# battery_monitor_6803-2.net
KiCad netlist of a schematic drawn in EAGLE
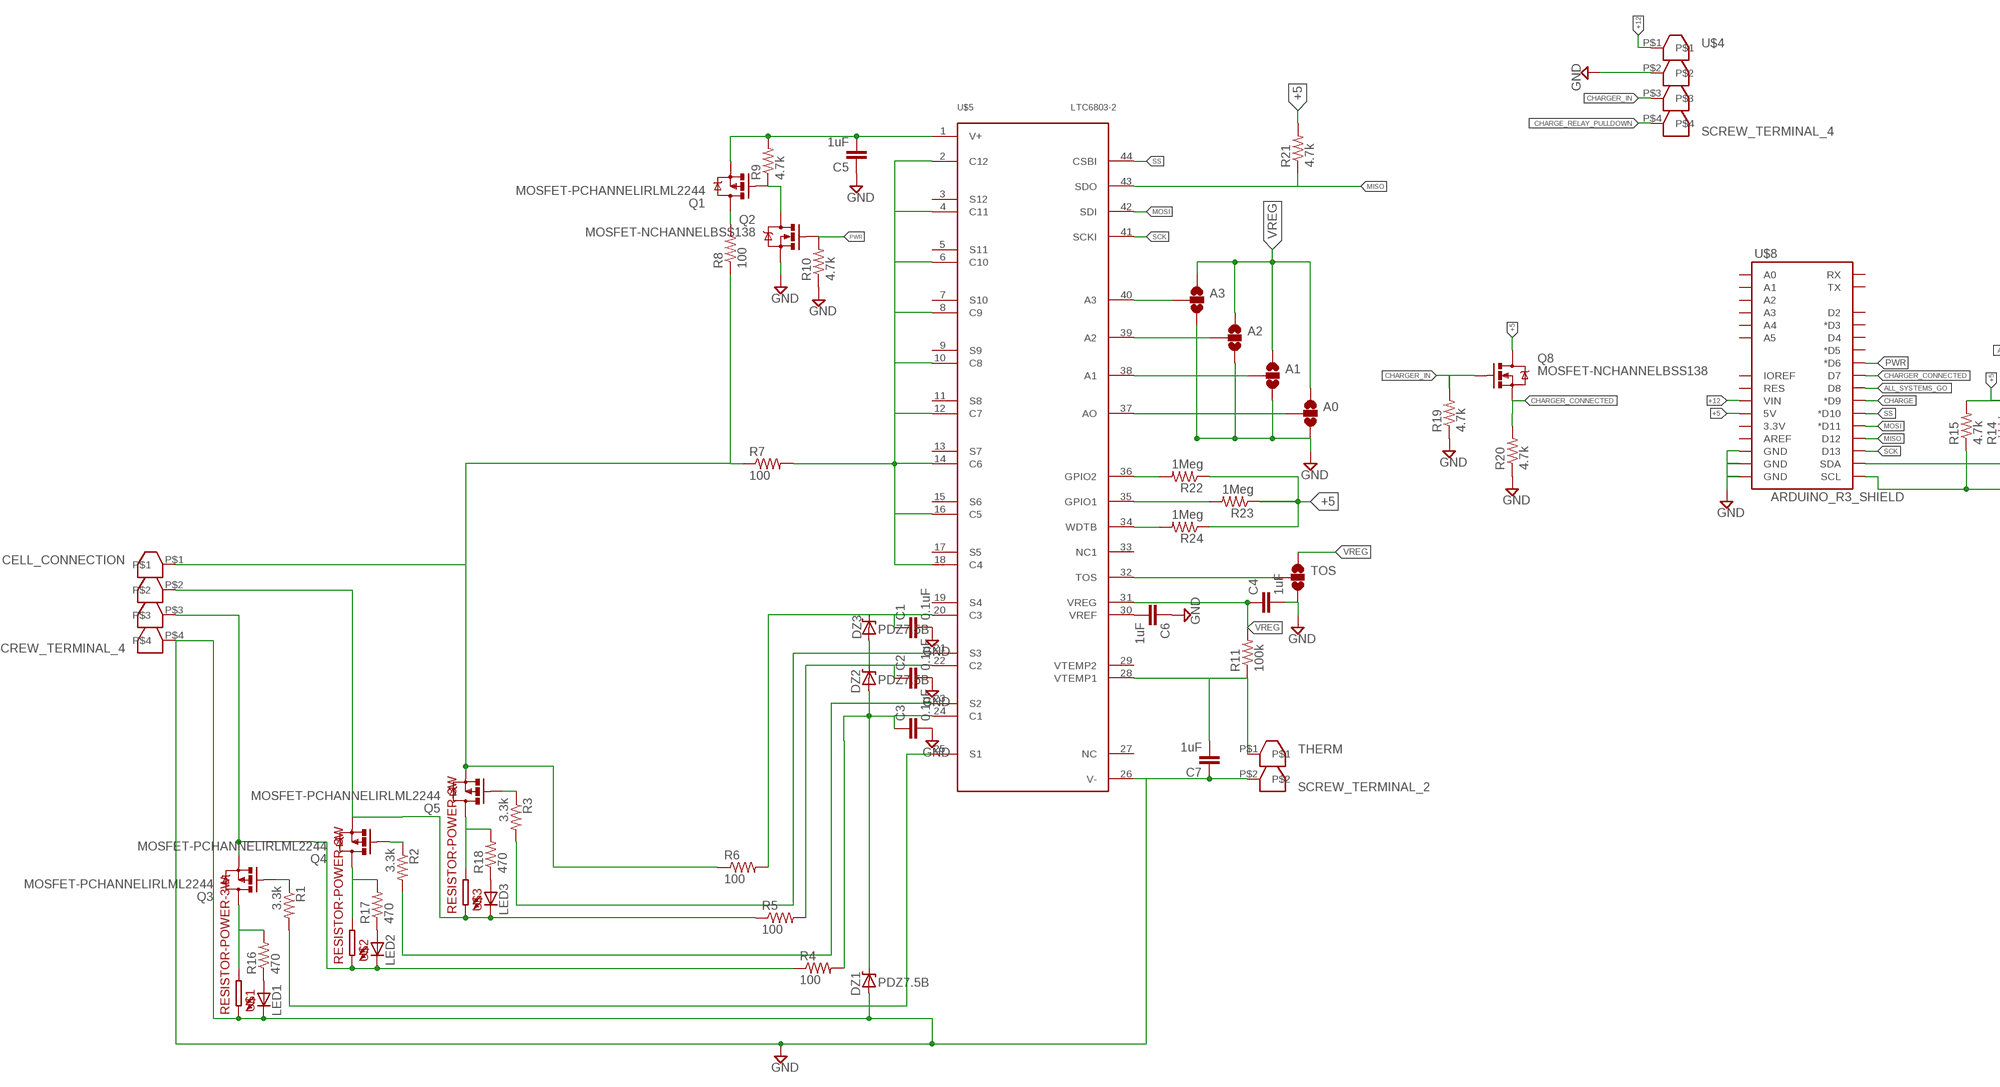
[diagram p0: schematic, sheet 1, part 1 of 2]
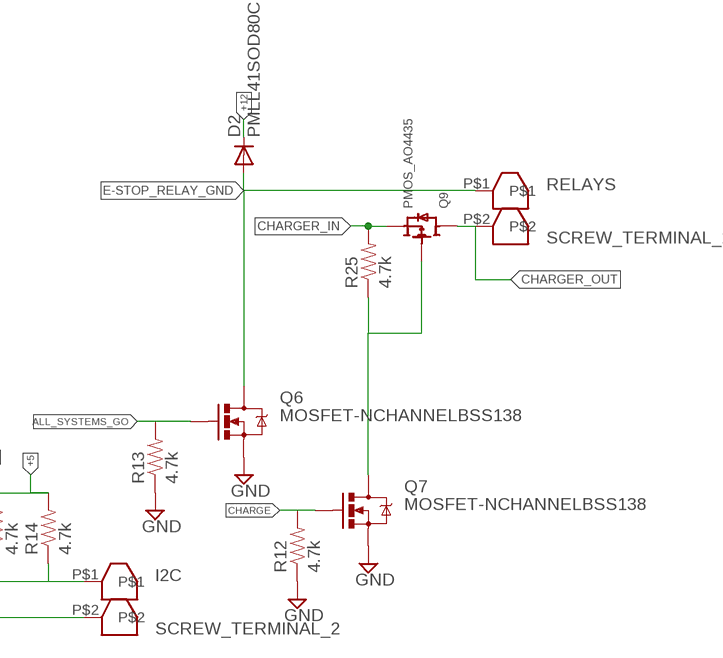
[diagram p1: schematic, sheet 1, part 2 of 2]

(export (version "E")
  (design (tool "Eeschema 10.0.6"))
  (components
    (comp (ref "A0")
      (value "SOLDERJUMPER_2WAYS")
      (footprint "eagle-import:SJ_3")
      (libsource (lib "eagle-import") (part "SOLDERJUMPER_2WAYS"))
    )
    (comp (ref "A1")
      (value "SOLDERJUMPER_2WAYS")
      (footprint "eagle-import:SJ_3")
      (libsource (lib "eagle-import") (part "SOLDERJUMPER_2WAYS"))
    )
    (comp (ref "A2")
      (value "SOLDERJUMPER_2WAYS")
      (footprint "eagle-import:SJ_3")
      (libsource (lib "eagle-import") (part "SOLDERJUMPER_2WAYS"))
    )
    (comp (ref "A3")
      (value "SOLDERJUMPER_2WAYS")
      (footprint "eagle-import:SJ_3")
      (libsource (lib "eagle-import") (part "SOLDERJUMPER_2WAYS"))
    )
    (comp (ref "C1")
      (value "0.1uF")
      (footprint "eagle-import:0603-CAP")
      (libsource (lib "eagle-import") (part "0.1UF-100V-10%(0603)"))
    )
    (comp (ref "C2")
      (value "0.1uF")
      (footprint "eagle-import:0603-CAP")
      (libsource (lib "eagle-import") (part "0.1UF-100V-10%(0603)"))
    )
    (comp (ref "C3")
      (value "0.1uF")
      (footprint "eagle-import:0603-CAP")
      (libsource (lib "eagle-import") (part "0.1UF-100V-10%(0603)"))
    )
    (comp (ref "C4")
      (value "1uF")
      (footprint "eagle-import:0603-CAP")
      (fields (field (name "PROD_ID") "CAP-08390"))
      (libsource (lib "eagle-import") (part "0.1UF-100V-10%(0603)"))
    )
    (comp (ref "C5")
      (value "1uF")
      (footprint "eagle-import:0603-CAP")
      (fields (field (name "PROD_ID") "CAP-08390"))
      (libsource (lib "eagle-import") (part "0.1UF-100V-10%(0603)"))
    )
    (comp (ref "C6")
      (value "1uF")
      (footprint "eagle-import:0603-CAP")
      (fields (field (name "PROD_ID") "CAP-08390"))
      (libsource (lib "eagle-import") (part "0.1UF-100V-10%(0603)"))
    )
    (comp (ref "C7")
      (value "1uF")
      (footprint "eagle-import:0603-CAP")
      (fields (field (name "PROD_ID") "CAP-08390"))
      (libsource (lib "eagle-import") (part "0.1UF-100V-10%(0603)"))
    )
    (comp (ref "CELL_CONNECTION")
      (value "SCREW_TERMINAL_4")
      (footprint "eagle-import:SCREW_TERMINAL_4")
      (libsource (lib "eagle-import") (part "SCREW_TERMINAL_4"))
    )
    (comp (ref "D2")
      (value "PMLL41SOD80C")
      (footprint "eagle-import:SOD80C")
      (libsource (lib "eagle-import") (part "PMLL41SOD80C"))
    )
    (comp (ref "DZ1")
      (value "PDZ7.5B")
      (footprint "eagle-import:SOD-323")
      (libsource (lib "eagle-import") (part "DIODE-ZENER-BZT52"))
    )
    (comp (ref "DZ2")
      (value "PDZ7.5B")
      (footprint "eagle-import:SOD-323")
      (libsource (lib "eagle-import") (part "DIODE-ZENER-BZT52"))
    )
    (comp (ref "DZ3")
      (value "PDZ7.5B")
      (footprint "eagle-import:SOD-323")
      (libsource (lib "eagle-import") (part "DIODE-ZENER-BZT52"))
    )
    (comp (ref "I2C")
      (value "SCREW_TERMINAL_2")
      (footprint "eagle-import:SCREW_TERMINAL_2")
      (libsource (lib "eagle-import") (part "SCREW_TERMINAL_2"))
    )
    (comp (ref "LED1")
      (value "LED0603")
      (footprint "eagle-import:LED-0603")
      (libsource (lib "eagle-import") (part "LED0603"))
    )
    (comp (ref "LED2")
      (value "LED0603")
      (footprint "eagle-import:LED-0603")
      (libsource (lib "eagle-import") (part "LED0603"))
    )
    (comp (ref "LED3")
      (value "LED0603")
      (footprint "eagle-import:LED-0603")
      (libsource (lib "eagle-import") (part "LED0603"))
    )
    (comp (ref "Q1")
      (value "MOSFET-PCHANNELIRLML2244")
      (footprint "eagle-import:SOT23-3")
      (libsource (lib "eagle-import") (part "MOSFET-PCHANNELIRLML2244"))
    )
    (comp (ref "Q2")
      (value "MOSFET-NCHANNELBSS138")
      (footprint "eagle-import:SOT23")
      (libsource (lib "eagle-import") (part "MOSFET-NCHANNELBSS138"))
    )
    (comp (ref "Q3")
      (value "MOSFET-PCHANNELIRLML2244")
      (footprint "eagle-import:SOT23-3")
      (libsource (lib "eagle-import") (part "MOSFET-PCHANNELIRLML2244"))
    )
    (comp (ref "Q4")
      (value "MOSFET-PCHANNELIRLML2244")
      (footprint "eagle-import:SOT23-3")
      (libsource (lib "eagle-import") (part "MOSFET-PCHANNELIRLML2244"))
    )
    (comp (ref "Q5")
      (value "MOSFET-PCHANNELIRLML2244")
      (footprint "eagle-import:SOT23-3")
      (libsource (lib "eagle-import") (part "MOSFET-PCHANNELIRLML2244"))
    )
    (comp (ref "Q6")
      (value "MOSFET-NCHANNELBSS138")
      (footprint "eagle-import:SOT23")
      (libsource (lib "eagle-import") (part "MOSFET-NCHANNELBSS138"))
    )
    (comp (ref "Q7")
      (value "MOSFET-NCHANNELBSS138")
      (footprint "eagle-import:SOT23")
      (libsource (lib "eagle-import") (part "MOSFET-NCHANNELBSS138"))
    )
    (comp (ref "Q8")
      (value "MOSFET-NCHANNELBSS138")
      (footprint "eagle-import:SOT23")
      (fields (field (name "PROD_ID") "TRANS-00830"))
      (libsource (lib "eagle-import") (part "MOSFET-NCHANNELBSS138"))
    )
    (comp (ref "Q9")
      (value "PMOS_AO4435")
      (footprint "eagle-import:SOIC8")
      (libsource (lib "eagle-import") (part "PMOS_AO4435"))
    )
    (comp (ref "R1")
      (value "3.3k")
      (footprint "eagle-import:0603-RES")
      (libsource (lib "eagle-import") (part "3.3KOHM1/10W1%(0603)"))
    )
    (comp (ref "R2")
      (value "3.3k")
      (footprint "eagle-import:0603-RES")
      (libsource (lib "eagle-import") (part "3.3KOHM1/10W1%(0603)"))
    )
    (comp (ref "R3")
      (value "3.3k")
      (footprint "eagle-import:0603-RES")
      (libsource (lib "eagle-import") (part "3.3KOHM1/10W1%(0603)"))
    )
    (comp (ref "R4")
      (value "100")
      (footprint "eagle-import:0603-RES")
      (libsource (lib "eagle-import") (part "3.3KOHM1/10W1%(0603)"))
    )
    (comp (ref "R5")
      (value "100")
      (footprint "eagle-import:0603-RES")
      (libsource (lib "eagle-import") (part "3.3KOHM1/10W1%(0603)"))
    )
    (comp (ref "R6")
      (value "100")
      (footprint "eagle-import:0603-RES")
      (libsource (lib "eagle-import") (part "3.3KOHM1/10W1%(0603)"))
    )
    (comp (ref "R7")
      (value "100")
      (footprint "eagle-import:0603-RES")
      (libsource (lib "eagle-import") (part "3.3KOHM1/10W1%(0603)"))
    )
    (comp (ref "R8")
      (value "100")
      (footprint "eagle-import:0603-RES")
      (libsource (lib "eagle-import") (part "3.3KOHM1/10W1%(0603)"))
    )
    (comp (ref "R9")
      (value "4.7k")
      (footprint "eagle-import:0603-RES")
      (libsource (lib "eagle-import") (part "3.3KOHM1/10W1%(0603)"))
    )
    (comp (ref "R10")
      (value "4.7k")
      (footprint "eagle-import:0603-RES")
      (libsource (lib "eagle-import") (part "3.3KOHM1/10W1%(0603)"))
    )
    (comp (ref "R11")
      (value "100k")
      (footprint "eagle-import:0603-RES")
      (libsource (lib "eagle-import") (part "3.3KOHM1/10W1%(0603)"))
    )
    (comp (ref "R12")
      (value "4.7k")
      (footprint "eagle-import:0603-RES")
      (libsource (lib "eagle-import") (part "3.3KOHM1/10W1%(0603)"))
    )
    (comp (ref "R13")
      (value "4.7k")
      (footprint "eagle-import:0603-RES")
      (libsource (lib "eagle-import") (part "3.3KOHM1/10W1%(0603)"))
    )
    (comp (ref "R14")
      (value "4.7k")
      (footprint "eagle-import:0603-RES")
      (libsource (lib "eagle-import") (part "3.3KOHM1/10W1%(0603)"))
    )
    (comp (ref "R15")
      (value "4.7k")
      (footprint "eagle-import:0603-RES")
      (libsource (lib "eagle-import") (part "3.3KOHM1/10W1%(0603)"))
    )
    (comp (ref "R16")
      (value "470")
      (footprint "eagle-import:0603-RES")
      (fields (field (name "PROD_ID") "RES-07851"))
      (libsource (lib "eagle-import") (part "3.3KOHM1/10W1%(0603)"))
    )
    (comp (ref "R17")
      (value "470")
      (footprint "eagle-import:0603-RES")
      (fields (field (name "PROD_ID") "RES-07851"))
      (libsource (lib "eagle-import") (part "3.3KOHM1/10W1%(0603)"))
    )
    (comp (ref "R18")
      (value "470")
      (footprint "eagle-import:0603-RES")
      (fields (field (name "PROD_ID") "RES-07851"))
      (libsource (lib "eagle-import") (part "3.3KOHM1/10W1%(0603)"))
    )
    (comp (ref "R19")
      (value "4.7k")
      (footprint "eagle-import:0603-RES")
      (fields (field (name "PROD_ID") "RES-07851"))
      (libsource (lib "eagle-import") (part "3.3KOHM1/10W1%(0603)"))
    )
    (comp (ref "R20")
      (value "4.7k")
      (footprint "eagle-import:0603-RES")
      (fields (field (name "PROD_ID") "RES-07851"))
      (libsource (lib "eagle-import") (part "3.3KOHM1/10W1%(0603)"))
    )
    (comp (ref "R21")
      (value "4.7k")
      (footprint "eagle-import:0603-RES")
      (fields (field (name "PROD_ID") "RES-07851"))
      (libsource (lib "eagle-import") (part "3.3KOHM1/10W1%(0603)"))
    )
    (comp (ref "R22")
      (value "1Meg")
      (footprint "eagle-import:0603-RES")
      (fields (field (name "PROD_ID") "RES-07851"))
      (libsource (lib "eagle-import") (part "3.3KOHM1/10W1%(0603)"))
    )
    (comp (ref "R23")
      (value "1Meg")
      (footprint "eagle-import:0603-RES")
      (fields (field (name "PROD_ID") "RES-07851"))
      (libsource (lib "eagle-import") (part "3.3KOHM1/10W1%(0603)"))
    )
    (comp (ref "R24")
      (value "1Meg")
      (footprint "eagle-import:0603-RES")
      (fields (field (name "PROD_ID") "RES-07851"))
      (libsource (lib "eagle-import") (part "3.3KOHM1/10W1%(0603)"))
    )
    (comp (ref "R25")
      (value "4.7k")
      (footprint "eagle-import:0603-RES")
      (fields (field (name "PROD_ID") "RES-07851"))
      (libsource (lib "eagle-import") (part "3.3KOHM1/10W1%(0603)"))
    )
    (comp (ref "RELAYS")
      (value "SCREW_TERMINAL_2")
      (footprint "eagle-import:SCREW_TERMINAL_2")
      (libsource (lib "eagle-import") (part "SCREW_TERMINAL_2"))
    )
    (comp (ref "THERM")
      (value "SCREW_TERMINAL_2")
      (footprint "eagle-import:SCREW_TERMINAL_2")
      (libsource (lib "eagle-import") (part "SCREW_TERMINAL_2"))
    )
    (comp (ref "TOS")
      (value "SOLDERJUMPER_2WAYS")
      (footprint "eagle-import:SJ_3")
      (libsource (lib "eagle-import") (part "SOLDERJUMPER_2WAYS"))
    )
    (comp (ref "U$1")
      (value "RESISTOR-POWER-3W")
      (footprint "eagle-import:RESISTOR-3W")
      (libsource (lib "eagle-import") (part "RESISTOR-POWER-3W"))
    )
    (comp (ref "U$2")
      (value "RESISTOR-POWER-3W")
      (footprint "eagle-import:RESISTOR-3W")
      (libsource (lib "eagle-import") (part "RESISTOR-POWER-3W"))
    )
    (comp (ref "U$3")
      (value "RESISTOR-POWER-3W")
      (footprint "eagle-import:RESISTOR-3W")
      (libsource (lib "eagle-import") (part "RESISTOR-POWER-3W"))
    )
    (comp (ref "U$4")
      (value "SCREW_TERMINAL_4")
      (footprint "eagle-import:SCREW_TERMINAL_4")
      (libsource (lib "eagle-import") (part "SCREW_TERMINAL_4"))
    )
    (comp (ref "U$5")
      (value "LTC6803-2")
      (footprint "eagle-import:FSOP-44")
      (libsource (lib "eagle-import") (part "LTC6803-2"))
    )
    (comp (ref "U$8")
      (value "ARDUINO_R3_SHIELD")
      (footprint "eagle-import:UNO_R3_SHIELD")
      (libsource (lib "eagle-import") (part "ARDUINO_R3_SHIELD"))
    )
  )
  (nets
    (net (code "1") (name "+5") (class "Default")
      (node (ref "Q8") (pin "3") (pinfunction "D_3") (pintype "passive"))
      (node (ref "R14") (pin "2") (pinfunction "2_2") (pintype "passive"))
      (node (ref "R15") (pin "2") (pinfunction "2_2") (pintype "passive"))
      (node (ref "R21") (pin "2") (pinfunction "2_2") (pintype "passive"))
      (node (ref "R22") (pin "1") (pinfunction "1_1") (pintype "passive"))
      (node (ref "R23") (pin "1") (pinfunction "1_1") (pintype "passive"))
      (node (ref "R24") (pin "1") (pinfunction "1_1") (pintype "passive"))
      (node (ref "U$8") (pin "5V") (pinfunction "5V_5V") (pintype "bidirectional"))
    )
    (net (code "2") (name "+12") (class "Default")
      (node (ref "D2") (pin "C") (pinfunction "C_C") (pintype "passive"))
      (node (ref "U$4") (pin "P$1") (pinfunction "P$1_P$1") (pintype "bidirectional"))
      (node (ref "U$8") (pin "VIN") (pinfunction "VIN_VIN") (pintype "bidirectional"))
    )
    (net (code "3") (name "ALL_SYSTEMS_GO") (class "Default")
      (node (ref "Q6") (pin "1") (pinfunction "G_1") (pintype "passive"))
      (node (ref "R13") (pin "2") (pinfunction "2_2") (pintype "passive"))
      (node (ref "U$8") (pin "D8") (pinfunction "D8_D8") (pintype "bidirectional"))
    )
    (net (code "4") (name "CHARGE") (class "Default")
      (node (ref "Q7") (pin "1") (pinfunction "G_1") (pintype "passive"))
      (node (ref "R12") (pin "2") (pinfunction "2_2") (pintype "passive"))
      (node (ref "U$8") (pin "D9") (pinfunction "*D9_D9") (pintype "bidirectional"))
    )
    (net (code "5") (name "CHARGER_CONNECTED") (class "Default")
      (node (ref "Q8") (pin "2") (pinfunction "S_2") (pintype "passive"))
      (node (ref "R20") (pin "2") (pinfunction "2_2") (pintype "passive"))
      (node (ref "U$8") (pin "D7") (pinfunction "D7_D7") (pintype "bidirectional"))
    )
    (net (code "6") (name "CHARGER_IN") (class "Default")
      (node (ref "Q8") (pin "1") (pinfunction "G_1") (pintype "passive"))
      (node (ref "Q9") (pin "1") (pinfunction "SOURCE_1") (pintype "bidirectional"))
      (node (ref "Q9") (pin "2") (pinfunction "SOURCE_2") (pintype "bidirectional"))
      (node (ref "Q9") (pin "3") (pinfunction "SOURCE_3") (pintype "bidirectional"))
      (node (ref "R19") (pin "2") (pinfunction "2_2") (pintype "passive"))
      (node (ref "R25") (pin "2") (pinfunction "2_2") (pintype "passive"))
      (node (ref "U$4") (pin "P$3") (pinfunction "P$3_P$3") (pintype "bidirectional"))
    )
    (net (code "7") (name "CHARGER_OUT") (class "Default")
      (node (ref "Q9") (pin "5") (pinfunction "DRAIN_5") (pintype "bidirectional"))
      (node (ref "Q9") (pin "6") (pinfunction "DRAIN_6") (pintype "bidirectional"))
      (node (ref "Q9") (pin "7") (pinfunction "DRAIN_7") (pintype "bidirectional"))
      (node (ref "Q9") (pin "8") (pinfunction "DRAIN_8") (pintype "bidirectional"))
      (node (ref "RELAYS") (pin "P$2") (pinfunction "P$2_P$2") (pintype "bidirectional"))
    )
    (net (code "8") (name "CHARGE_RELAY_PULLDOWN") (class "Default")
      (node (ref "U$4") (pin "P$4") (pinfunction "P$4_P$4") (pintype "bidirectional"))
    )
    (net (code "9") (name "E-STOP_RELAY_GND") (class "Default")
      (node (ref "D2") (pin "A") (pinfunction "A_A") (pintype "passive"))
      (node (ref "Q6") (pin "3") (pinfunction "D_3") (pintype "passive"))
      (node (ref "RELAYS") (pin "P$1") (pinfunction "P$1_P$1") (pintype "bidirectional"))
    )
    (net (code "10") (name "GND") (class "Default")
      (node (ref "A0") (pin "3") (pinfunction "3_3") (pintype "passive"))
      (node (ref "A1") (pin "3") (pinfunction "3_3") (pintype "passive"))
      (node (ref "A2") (pin "3") (pinfunction "3_3") (pintype "passive"))
      (node (ref "A3") (pin "3") (pinfunction "3_3") (pintype "passive"))
      (node (ref "C1") (pin "2") (pinfunction "2_2") (pintype "passive"))
      (node (ref "C2") (pin "2") (pinfunction "2_2") (pintype "passive"))
      (node (ref "C3") (pin "2") (pinfunction "2_2") (pintype "passive"))
      (node (ref "C4") (pin "2") (pinfunction "2_2") (pintype "passive"))
      (node (ref "C5") (pin "1") (pinfunction "1_1") (pintype "passive"))
      (node (ref "C6") (pin "1") (pinfunction "1_1") (pintype "passive"))
      (node (ref "C7") (pin "1") (pinfunction "1_1") (pintype "passive"))
      (node (ref "CELL_CONNECTION") (pin "P$4") (pinfunction "P$4_P$4") (pintype "bidirectional"))
      (node (ref "DZ1") (pin "2") (pinfunction "A_2") (pintype "passive"))
      (node (ref "LED1") (pin "C") (pinfunction "C_C") (pintype "passive"))
      (node (ref "Q2") (pin "2") (pinfunction "S_2") (pintype "passive"))
      (node (ref "Q6") (pin "2") (pinfunction "S_2") (pintype "passive"))
      (node (ref "Q7") (pin "2") (pinfunction "S_2") (pintype "passive"))
      (node (ref "R10") (pin "1") (pinfunction "1_1") (pintype "passive"))
      (node (ref "R12") (pin "1") (pinfunction "1_1") (pintype "passive"))
      (node (ref "R13") (pin "1") (pinfunction "1_1") (pintype "passive"))
      (node (ref "R19") (pin "1") (pinfunction "1_1") (pintype "passive"))
      (node (ref "R20") (pin "1") (pinfunction "1_1") (pintype "passive"))
      (node (ref "THERM") (pin "P$2") (pinfunction "P$2_P$2") (pintype "bidirectional"))
      (node (ref "TOS") (pin "3") (pinfunction "3_3") (pintype "passive"))
      (node (ref "U$1") (pin "P$2") (pinfunction "P$2_P$2") (pintype "bidirectional"))
      (node (ref "U$4") (pin "P$2") (pinfunction "P$2_P$2") (pintype "bidirectional"))
      (node (ref "U$5") (pin "26") (pinfunction "V-_26") (pintype "bidirectional"))
      (node (ref "U$8") (pin "GND@0") (pinfunction "GND_GND@0") (pintype "bidirectional"))
      (node (ref "U$8") (pin "GND@1") (pinfunction "GND_GND@1") (pintype "bidirectional"))
      (node (ref "U$8") (pin "GND@2") (pinfunction "GND_GND@2") (pintype "bidirectional"))
    )
    (net (code "11") (name "MISO") (class "Default")
      (node (ref "R21") (pin "1") (pinfunction "1_1") (pintype "passive"))
      (node (ref "U$5") (pin "43") (pinfunction "SDO_43") (pintype "bidirectional"))
      (node (ref "U$8") (pin "D12") (pinfunction "D12_D12") (pintype "bidirectional"))
    )
    (net (code "12") (name "MOSI") (class "Default")
      (node (ref "U$5") (pin "42") (pinfunction "SDI_42") (pintype "bidirectional"))
      (node (ref "U$8") (pin "D11") (pinfunction "*D11_D11") (pintype "bidirectional"))
    )
    (net (code "13") (name "Net-(DZ1-C)") (class "Default")
      (node (ref "C3") (pin "1") (pinfunction "1_1") (pintype "passive"))
      (node (ref "DZ1") (pin "1") (pinfunction "C_1") (pintype "passive"))
      (node (ref "DZ2") (pin "2") (pinfunction "A_2") (pintype "passive"))
      (node (ref "R4") (pin "2") (pinfunction "2_2") (pintype "passive"))
      (node (ref "U$5") (pin "24") (pinfunction "C1_24") (pintype "bidirectional"))
    )
    (net (code "14") (name "Net-(DZ2-C)") (class "Default")
      (node (ref "C2") (pin "1") (pinfunction "1_1") (pintype "passive"))
      (node (ref "DZ2") (pin "1") (pinfunction "C_1") (pintype "passive"))
      (node (ref "DZ3") (pin "2") (pinfunction "A_2") (pintype "passive"))
      (node (ref "R5") (pin "2") (pinfunction "2_2") (pintype "passive"))
      (node (ref "U$5") (pin "22") (pinfunction "C2_22") (pintype "bidirectional"))
    )
    (net (code "15") (name "Net-(DZ3-C)") (class "Default")
      (node (ref "C1") (pin "1") (pinfunction "1_1") (pintype "passive"))
      (node (ref "DZ3") (pin "1") (pinfunction "C_1") (pintype "passive"))
      (node (ref "R6") (pin "2") (pinfunction "2_2") (pintype "passive"))
      (node (ref "U$5") (pin "20") (pinfunction "C3_20") (pintype "bidirectional"))
    )
    (net (code "16") (name "Net-(I2C-PadP$1)") (class "Default")
      (node (ref "I2C") (pin "P$1") (pinfunction "P$1_P$1") (pintype "bidirectional"))
      (node (ref "R14") (pin "1") (pinfunction "1_1") (pintype "passive"))
      (node (ref "U$8") (pin "SDA") (pinfunction "SDA_SDA") (pintype "bidirectional"))
    )
    (net (code "17") (name "Net-(I2C-PadP$2)") (class "Default")
      (node (ref "I2C") (pin "P$2") (pinfunction "P$2_P$2") (pintype "bidirectional"))
      (node (ref "R15") (pin "1") (pinfunction "1_1") (pintype "passive"))
      (node (ref "U$8") (pin "SCL") (pinfunction "SCL_SCL") (pintype "bidirectional"))
    )
    (net (code "18") (name "Net-(LED1-PadA)") (class "Default")
      (node (ref "LED1") (pin "A") (pinfunction "A_A") (pintype "passive"))
      (node (ref "R16") (pin "1") (pinfunction "1_1") (pintype "passive"))
    )
    (net (code "19") (name "Net-(LED2-PadA)") (class "Default")
      (node (ref "LED2") (pin "A") (pinfunction "A_A") (pintype "passive"))
      (node (ref "R17") (pin "1") (pinfunction "1_1") (pintype "passive"))
    )
    (net (code "20") (name "Net-(LED3-PadA)") (class "Default")
      (node (ref "LED3") (pin "A") (pinfunction "A_A") (pintype "passive"))
      (node (ref "R18") (pin "1") (pinfunction "1_1") (pintype "passive"))
    )
    (net (code "21") (name "Net-(Q1-D)") (class "Default")
      (node (ref "Q1") (pin "3") (pinfunction "D_3") (pintype "passive"))
      (node (ref "R8") (pin "2") (pinfunction "2_2") (pintype "passive"))
    )
    (net (code "22") (name "Net-(Q1-G)") (class "Default")
      (node (ref "Q1") (pin "1") (pinfunction "G_1") (pintype "passive"))
      (node (ref "Q2") (pin "3") (pinfunction "D_3") (pintype "passive"))
      (node (ref "R9") (pin "1") (pinfunction "1_1") (pintype "passive"))
    )
    (net (code "23") (name "Net-(Q1-S)") (class "Default")
      (node (ref "C5") (pin "2") (pinfunction "2_2") (pintype "passive"))
      (node (ref "Q1") (pin "2") (pinfunction "S_2") (pintype "passive"))
      (node (ref "R9") (pin "2") (pinfunction "2_2") (pintype "passive"))
      (node (ref "U$5") (pin "1") (pinfunction "V+_1") (pintype "bidirectional"))
    )
    (net (code "24") (name "Net-(Q3-D)") (class "Default")
      (node (ref "Q3") (pin "3") (pinfunction "D_3") (pintype "passive"))
      (node (ref "R16") (pin "2") (pinfunction "2_2") (pintype "passive"))
      (node (ref "U$1") (pin "P$1") (pinfunction "P$1_P$1") (pintype "bidirectional"))
    )
    (net (code "25") (name "Net-(Q3-G)") (class "Default")
      (node (ref "Q3") (pin "1") (pinfunction "G_1") (pintype "passive"))
      (node (ref "R1") (pin "1") (pinfunction "1_1") (pintype "passive"))
    )
    (net (code "26") (name "Net-(Q3-S)") (class "Default")
      (node (ref "CELL_CONNECTION") (pin "P$3") (pinfunction "P$3_P$3") (pintype "bidirectional"))
      (node (ref "LED2") (pin "C") (pinfunction "C_C") (pintype "passive"))
      (node (ref "Q3") (pin "2") (pinfunction "S_2") (pintype "passive"))
      (node (ref "R4") (pin "1") (pinfunction "1_1") (pintype "passive"))
      (node (ref "U$2") (pin "P$2") (pinfunction "P$2_P$2") (pintype "bidirectional"))
    )
    (net (code "27") (name "Net-(Q4-D)") (class "Default")
      (node (ref "Q4") (pin "3") (pinfunction "D_3") (pintype "passive"))
      (node (ref "R17") (pin "2") (pinfunction "2_2") (pintype "passive"))
      (node (ref "U$2") (pin "P$1") (pinfunction "P$1_P$1") (pintype "bidirectional"))
    )
    (net (code "28") (name "Net-(Q4-G)") (class "Default")
      (node (ref "Q4") (pin "1") (pinfunction "G_1") (pintype "passive"))
      (node (ref "R2") (pin "1") (pinfunction "1_1") (pintype "passive"))
    )
    (net (code "29") (name "Net-(Q4-S)") (class "Default")
      (node (ref "CELL_CONNECTION") (pin "P$2") (pinfunction "P$2_P$2") (pintype "bidirectional"))
      (node (ref "LED3") (pin "C") (pinfunction "C_C") (pintype "passive"))
      (node (ref "Q4") (pin "2") (pinfunction "S_2") (pintype "passive"))
      (node (ref "R5") (pin "1") (pinfunction "1_1") (pintype "passive"))
      (node (ref "U$3") (pin "P$2") (pinfunction "P$2_P$2") (pintype "bidirectional"))
    )
    (net (code "30") (name "Net-(Q5-D)") (class "Default")
      (node (ref "Q5") (pin "3") (pinfunction "D_3") (pintype "passive"))
      (node (ref "R18") (pin "2") (pinfunction "2_2") (pintype "passive"))
      (node (ref "U$3") (pin "P$1") (pinfunction "P$1_P$1") (pintype "bidirectional"))
    )
    (net (code "31") (name "Net-(Q5-G)") (class "Default")
      (node (ref "Q5") (pin "1") (pinfunction "G_1") (pintype "passive"))
      (node (ref "R3") (pin "1") (pinfunction "1_1") (pintype "passive"))
    )
    (net (code "32") (name "Net-(Q5-S)") (class "Default")
      (node (ref "CELL_CONNECTION") (pin "P$1") (pinfunction "P$1_P$1") (pintype "bidirectional"))
      (node (ref "Q5") (pin "2") (pinfunction "S_2") (pintype "passive"))
      (node (ref "R6") (pin "1") (pinfunction "1_1") (pintype "passive"))
      (node (ref "R7") (pin "1") (pinfunction "1_1") (pintype "passive"))
      (node (ref "R8") (pin "1") (pinfunction "1_1") (pintype "passive"))
    )
    (net (code "33") (name "Net-(Q7-D)") (class "Default")
      (node (ref "Q7") (pin "3") (pinfunction "D_3") (pintype "passive"))
      (node (ref "Q9") (pin "4") (pinfunction "GATE_4") (pintype "bidirectional"))
      (node (ref "R25") (pin "1") (pinfunction "1_1") (pintype "passive"))
    )
    (net (code "34") (name "Net-(U$5-A1)") (class "Default")
      (node (ref "A1") (pin "2") (pinfunction "2_2") (pintype "passive"))
      (node (ref "U$5") (pin "38") (pinfunction "A1_38") (pintype "bidirectional"))
    )
    (net (code "35") (name "Net-(U$5-A2)") (class "Default")
      (node (ref "A2") (pin "2") (pinfunction "2_2") (pintype "passive"))
      (node (ref "U$5") (pin "39") (pinfunction "A2_39") (pintype "bidirectional"))
    )
    (net (code "36") (name "Net-(U$5-A3)") (class "Default")
      (node (ref "A3") (pin "2") (pinfunction "2_2") (pintype "passive"))
      (node (ref "U$5") (pin "40") (pinfunction "A3_40") (pintype "bidirectional"))
    )
    (net (code "37") (name "Net-(U$5-AO)") (class "Default")
      (node (ref "A0") (pin "2") (pinfunction "2_2") (pintype "passive"))
      (node (ref "U$5") (pin "37") (pinfunction "AO_37") (pintype "bidirectional"))
    )
    (net (code "38") (name "Net-(U$5-C10)") (class "Default")
      (node (ref "R7") (pin "2") (pinfunction "2_2") (pintype "passive"))
      (node (ref "U$5") (pin "10") (pinfunction "C8_10") (pintype "bidirectional"))
      (node (ref "U$5") (pin "12") (pinfunction "C7_12") (pintype "bidirectional"))
      (node (ref "U$5") (pin "14") (pinfunction "C6_14") (pintype "bidirectional"))
      (node (ref "U$5") (pin "16") (pinfunction "C5_16") (pintype "bidirectional"))
      (node (ref "U$5") (pin "18") (pinfunction "C4_18") (pintype "bidirectional"))
      (node (ref "U$5") (pin "2") (pinfunction "C12_2") (pintype "bidirectional"))
      (node (ref "U$5") (pin "4") (pinfunction "C11_4") (pintype "bidirectional"))
      (node (ref "U$5") (pin "6") (pinfunction "C10_6") (pintype "bidirectional"))
      (node (ref "U$5") (pin "8") (pinfunction "C9_8") (pintype "bidirectional"))
    )
    (net (code "39") (name "Net-(U$5-GPIO1)") (class "Default")
      (node (ref "R23") (pin "2") (pinfunction "2_2") (pintype "passive"))
      (node (ref "U$5") (pin "35") (pinfunction "GPIO1_35") (pintype "bidirectional"))
    )
    (net (code "40") (name "Net-(U$5-GPIO2)") (class "Default")
      (node (ref "R22") (pin "2") (pinfunction "2_2") (pintype "passive"))
      (node (ref "U$5") (pin "36") (pinfunction "GPIO2_36") (pintype "bidirectional"))
    )
    (net (code "41") (name "Net-(U$5-S1)") (class "Default")
      (node (ref "R1") (pin "2") (pinfunction "2_2") (pintype "passive"))
      (node (ref "U$5") (pin "25") (pinfunction "S1_25") (pintype "bidirectional"))
    )
    (net (code "42") (name "Net-(U$5-S2)") (class "Default")
      (node (ref "R2") (pin "2") (pinfunction "2_2") (pintype "passive"))
      (node (ref "U$5") (pin "23") (pinfunction "S2_23") (pintype "bidirectional"))
    )
    (net (code "43") (name "Net-(U$5-S3)") (class "Default")
      (node (ref "R3") (pin "2") (pinfunction "2_2") (pintype "passive"))
      (node (ref "U$5") (pin "21") (pinfunction "S3_21") (pintype "bidirectional"))
    )
    (net (code "44") (name "Net-(U$5-TOS)") (class "Default")
      (node (ref "TOS") (pin "2") (pinfunction "2_2") (pintype "passive"))
      (node (ref "U$5") (pin "32") (pinfunction "TOS_32") (pintype "bidirectional"))
    )
    (net (code "45") (name "Net-(U$5-VREF)") (class "Default")
      (node (ref "C6") (pin "2") (pinfunction "2_2") (pintype "passive"))
      (node (ref "U$5") (pin "30") (pinfunction "VREF_30") (pintype "bidirectional"))
    )
    (net (code "46") (name "Net-(U$5-VTEMP1)") (class "Default")
      (node (ref "C7") (pin "2") (pinfunction "2_2") (pintype "passive"))
      (node (ref "R11") (pin "1") (pinfunction "1_1") (pintype "passive"))
      (node (ref "THERM") (pin "P$1") (pinfunction "P$1_P$1") (pintype "bidirectional"))
      (node (ref "U$5") (pin "28") (pinfunction "VTEMP1_28") (pintype "bidirectional"))
    )
    (net (code "47") (name "Net-(U$5-WDTB)") (class "Default")
      (node (ref "R24") (pin "2") (pinfunction "2_2") (pintype "passive"))
      (node (ref "U$5") (pin "34") (pinfunction "WDTB_34") (pintype "bidirectional"))
    )
    (net (code "48") (name "PWR") (class "Default")
      (node (ref "Q2") (pin "1") (pinfunction "G_1") (pintype "passive"))
      (node (ref "R10") (pin "2") (pinfunction "2_2") (pintype "passive"))
      (node (ref "U$8") (pin "D6") (pinfunction "*D6_D6") (pintype "bidirectional"))
    )
    (net (code "49") (name "SCK") (class "Default")
      (node (ref "U$5") (pin "41") (pinfunction "SCKI_41") (pintype "bidirectional"))
      (node (ref "U$8") (pin "D13") (pinfunction "D13_D13") (pintype "bidirectional"))
    )
    (net (code "50") (name "SS") (class "Default")
      (node (ref "U$5") (pin "44") (pinfunction "CSBI_44") (pintype "bidirectional"))
      (node (ref "U$8") (pin "D10") (pinfunction "*D10_D10") (pintype "bidirectional"))
    )
    (net (code "51") (name "VREG") (class "Default")
      (node (ref "A0") (pin "1") (pinfunction "1_1") (pintype "passive"))
      (node (ref "A1") (pin "1") (pinfunction "1_1") (pintype "passive"))
      (node (ref "A2") (pin "1") (pinfunction "1_1") (pintype "passive"))
      (node (ref "A3") (pin "1") (pinfunction "1_1") (pintype "passive"))
      (node (ref "C4") (pin "1") (pinfunction "1_1") (pintype "passive"))
      (node (ref "R11") (pin "2") (pinfunction "2_2") (pintype "passive"))
      (node (ref "TOS") (pin "1") (pinfunction "1_1") (pintype "passive"))
      (node (ref "U$5") (pin "31") (pinfunction "VREG_31") (pintype "bidirectional"))
    )
    (net (code "52") (name "unconnected-(U$5-NC-Pad27)") (class "Default")
      (node (ref "U$5") (pin "27") (pinfunction "NC_27") (pintype "bidirectional"))
    )
    (net (code "53") (name "unconnected-(U$5-NC1-Pad33)") (class "Default")
      (node (ref "U$5") (pin "33") (pinfunction "NC1_33") (pintype "bidirectional"))
    )
    (net (code "54") (name "unconnected-(U$5-S4-Pad19)") (class "Default")
      (node (ref "U$5") (pin "19") (pinfunction "S4_19") (pintype "bidirectional"))
    )
    (net (code "55") (name "unconnected-(U$5-S5-Pad17)") (class "Default")
      (node (ref "U$5") (pin "17") (pinfunction "S5_17") (pintype "bidirectional"))
    )
    (net (code "56") (name "unconnected-(U$5-S6-Pad15)") (class "Default")
      (node (ref "U$5") (pin "15") (pinfunction "S6_15") (pintype "bidirectional"))
    )
    (net (code "57") (name "unconnected-(U$5-S7-Pad13)") (class "Default")
      (node (ref "U$5") (pin "13") (pinfunction "S7_13") (pintype "bidirectional"))
    )
    (net (code "58") (name "unconnected-(U$5-S8-Pad11)") (class "Default")
      (node (ref "U$5") (pin "11") (pinfunction "S8_11") (pintype "bidirectional"))
    )
    (net (code "59") (name "unconnected-(U$5-S9-Pad9)") (class "Default")
      (node (ref "U$5") (pin "9") (pinfunction "S9_9") (pintype "bidirectional"))
    )
    (net (code "60") (name "unconnected-(U$5-S10-Pad7)") (class "Default")
      (node (ref "U$5") (pin "7") (pinfunction "S10_7") (pintype "bidirectional"))
    )
    (net (code "61") (name "unconnected-(U$5-S11-Pad5)") (class "Default")
      (node (ref "U$5") (pin "5") (pinfunction "S11_5") (pintype "bidirectional"))
    )
    (net (code "62") (name "unconnected-(U$5-S12-Pad3)") (class "Default")
      (node (ref "U$5") (pin "3") (pinfunction "S12_3") (pintype "bidirectional"))
    )
    (net (code "63") (name "unconnected-(U$5-VTEMP2-Pad29)") (class "Default")
      (node (ref "U$5") (pin "29") (pinfunction "VTEMP2_29") (pintype "bidirectional"))
    )
    (net (code "64") (name "unconnected-(U$8-*D3-PadD3)") (class "Default")
      (node (ref "U$8") (pin "D3") (pinfunction "*D3_D3") (pintype "bidirectional"))
    )
    (net (code "65") (name "unconnected-(U$8-*D5-PadD5)") (class "Default")
      (node (ref "U$8") (pin "D5") (pinfunction "*D5_D5") (pintype "bidirectional"))
    )
    (net (code "66") (name "unconnected-(U$8-Pad3.3V)") (class "Default")
      (node (ref "U$8") (pin "3.3V") (pinfunction "3.3V_3.3V") (pintype "bidirectional"))
    )
    (net (code "67") (name "unconnected-(U$8-PadA0)") (class "Default")
      (node (ref "U$8") (pin "A0") (pinfunction "A0_A0") (pintype "bidirectional"))
    )
    (net (code "68") (name "unconnected-(U$8-PadA1)") (class "Default")
      (node (ref "U$8") (pin "A1") (pinfunction "A1_A1") (pintype "bidirectional"))
    )
    (net (code "69") (name "unconnected-(U$8-PadA2)") (class "Default")
      (node (ref "U$8") (pin "A2") (pinfunction "A2_A2") (pintype "bidirectional"))
    )
    (net (code "70") (name "unconnected-(U$8-PadA3)") (class "Default")
      (node (ref "U$8") (pin "A3") (pinfunction "A3_A3") (pintype "bidirectional"))
    )
    (net (code "71") (name "unconnected-(U$8-PadA4)") (class "Default")
      (node (ref "U$8") (pin "A4") (pinfunction "A4_A4") (pintype "bidirectional"))
    )
    (net (code "72") (name "unconnected-(U$8-PadA5)") (class "Default")
      (node (ref "U$8") (pin "A5") (pinfunction "A5_A5") (pintype "bidirectional"))
    )
    (net (code "73") (name "unconnected-(U$8-PadAREF)") (class "Default")
      (node (ref "U$8") (pin "AREF") (pinfunction "AREF_AREF") (pintype "bidirectional"))
    )
    (net (code "74") (name "unconnected-(U$8-PadD2)") (class "Default")
      (node (ref "U$8") (pin "D2") (pinfunction "D2_D2") (pintype "bidirectional"))
    )
    (net (code "75") (name "unconnected-(U$8-PadD4)") (class "Default")
      (node (ref "U$8") (pin "D4") (pinfunction "D4_D4") (pintype "bidirectional"))
    )
    (net (code "76") (name "unconnected-(U$8-PadIOREF)") (class "Default")
      (node (ref "U$8") (pin "IOREF") (pinfunction "IOREF_IOREF") (pintype "bidirectional"))
    )
    (net (code "77") (name "unconnected-(U$8-PadRES)") (class "Default")
      (node (ref "U$8") (pin "RES") (pinfunction "RES_RES") (pintype "bidirectional"))
    )
    (net (code "78") (name "unconnected-(U$8-PadRX)") (class "Default")
      (node (ref "U$8") (pin "RX") (pinfunction "RX_RX") (pintype "bidirectional"))
    )
    (net (code "79") (name "unconnected-(U$8-PadTX)") (class "Default")
      (node (ref "U$8") (pin "TX") (pinfunction "TX_TX") (pintype "bidirectional"))
    )
  )
)
